# MainBoard.net
KiCad netlist of a schematic drawn in EAGLE
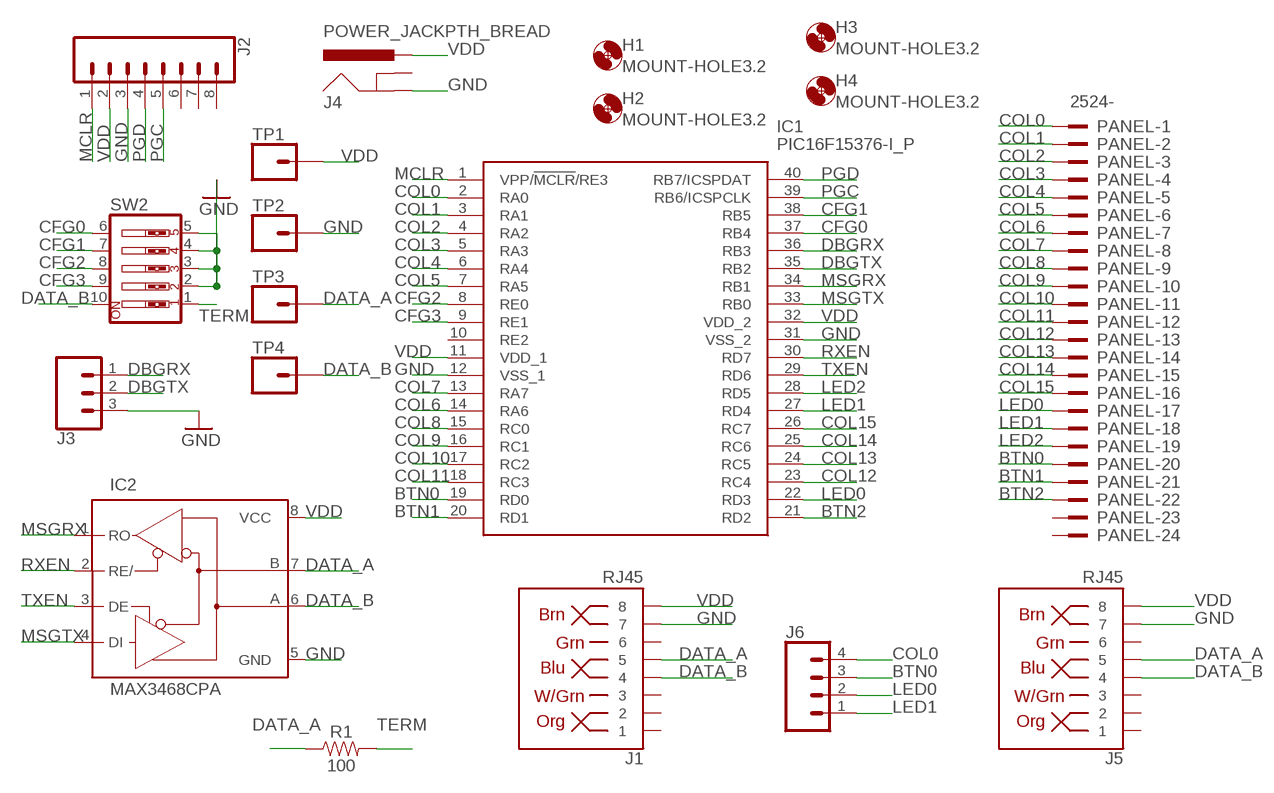
[diagram p0: schematic, sheet 1]

(export (version "E")
  (design (tool "Eeschema 10.0.6"))
  (components
    (comp (ref "H1")
      (value "MOUNT-HOLE3.2")
      (footprint "eagle-import:3,2")
      (libsource (lib "eagle-import") (part "MOUNT-HOLE3.2"))
    )
    (comp (ref "H2")
      (value "MOUNT-HOLE3.2")
      (footprint "eagle-import:3,2")
      (libsource (lib "eagle-import") (part "MOUNT-HOLE3.2"))
    )
    (comp (ref "H3")
      (value "MOUNT-HOLE3.2")
      (footprint "eagle-import:3,2")
      (libsource (lib "eagle-import") (part "MOUNT-HOLE3.2"))
    )
    (comp (ref "H4")
      (value "MOUNT-HOLE3.2")
      (footprint "eagle-import:3,2")
      (libsource (lib "eagle-import") (part "MOUNT-HOLE3.2"))
    )
    (comp (ref "IC1")
      (value "PIC16F15376-I_P")
      (footprint "eagle-import:DIP1550W56P254L5219H483Q40N")
      (fields (field (name "MANUFACTURER_PART_NUMBER") "PIC16F15376-I/P"))
      (libsource (lib "eagle-import") (part "PIC16F15376-I_P"))
    )
    (comp (ref "IC2")
      (value "MAX3468CPA")
      (footprint "eagle-import:DIL08")
      (libsource (lib "eagle-import") (part "MAX34PA68C"))
    )
    (comp (ref "J1")
      (value "RJ45")
      (footprint "eagle-import:RJ45-8")
      (libsource (lib "eagle-import") (part "RJ45-8"))
    )
    (comp (ref "J2")
      (value "CONN_08\"")
      (footprint "eagle-import:1X08")
      (libsource (lib "eagle-import") (part "CONN_08{dblquote}"))
    )
    (comp (ref "J3")
      (value "CONN_03")
      (footprint "eagle-import:1X03")
      (libsource (lib "eagle-import") (part "CONN_03"))
    )
    (comp (ref "J4")
      (value "POWER_JACKPTH_BREAD")
      (footprint "eagle-import:POWER_JACK_PTH_BREAD")
      (libsource (lib "eagle-import") (part "POWER_JACKPTH_BREAD"))
    )
    (comp (ref "J5")
      (value "RJ45")
      (footprint "eagle-import:RJ45-8")
      (libsource (lib "eagle-import") (part "RJ45-8"))
    )
    (comp (ref "J6")
      (value "CONN_04")
      (footprint "eagle-import:1X04")
      (libsource (lib "eagle-import") (part "CONN_04"))
    )
    (comp (ref "PANEL")
      (value "2524-")
      (footprint "eagle-import:PAK100_2500-24")
      (libsource (lib "eagle-import") (part "2524-"))
    )
    (comp (ref "R1")
      (value "100")
      (footprint "eagle-import:AXIAL-0.3")
      (libsource (lib "eagle-import") (part "100OHM-HORIZ-1/4W-1%"))
    )
    (comp (ref "SW2")
      (value "SW_DIP-5")
      (footprint "eagle-import:EDG-05")
      (libsource (lib "eagle-import") (part "SW_DIP-5"))
    )
    (comp (ref "TP1")
      (value "CONN_01")
      (footprint "eagle-import:1X01")
      (libsource (lib "eagle-import") (part "CONN_01"))
    )
    (comp (ref "TP2")
      (value "CONN_01")
      (footprint "eagle-import:1X01")
      (libsource (lib "eagle-import") (part "CONN_01"))
    )
    (comp (ref "TP3")
      (value "CONN_01")
      (footprint "eagle-import:1X01")
      (libsource (lib "eagle-import") (part "CONN_01"))
    )
    (comp (ref "TP4")
      (value "CONN_01")
      (footprint "eagle-import:1X01")
      (libsource (lib "eagle-import") (part "CONN_01"))
    )
  )
  (nets
    (net (code "1") (name "/BTN0") (class "Default")
      (node (ref "IC1") (pin "19") (pinfunction "RD0_19") (pintype "bidirectional"))
      (node (ref "J6") (pin "3") (pinfunction "3_3") (pintype "passive"))
      (node (ref "PANEL") (pin "20") (pinfunction "KL_20") (pintype "passive"))
    )
    (net (code "2") (name "/BTN1") (class "Default")
      (node (ref "IC1") (pin "20") (pinfunction "RD1_20") (pintype "bidirectional"))
      (node (ref "PANEL") (pin "21") (pinfunction "KL_21") (pintype "passive"))
    )
    (net (code "3") (name "/BTN2") (class "Default")
      (node (ref "IC1") (pin "21") (pinfunction "RD2_21") (pintype "bidirectional"))
      (node (ref "PANEL") (pin "22") (pinfunction "KL_22") (pintype "passive"))
    )
    (net (code "4") (name "/CFG0") (class "Default")
      (node (ref "IC1") (pin "37") (pinfunction "RB4_37") (pintype "bidirectional"))
      (node (ref "SW2") (pin "6") (pinfunction "6_6") (pintype "passive"))
    )
    (net (code "5") (name "/CFG1") (class "Default")
      (node (ref "IC1") (pin "38") (pinfunction "RB5_38") (pintype "bidirectional"))
      (node (ref "SW2") (pin "7") (pinfunction "7_7") (pintype "passive"))
    )
    (net (code "6") (name "/CFG2") (class "Default")
      (node (ref "IC1") (pin "8") (pinfunction "RE0_8") (pintype "bidirectional"))
      (node (ref "SW2") (pin "8") (pinfunction "8_8") (pintype "passive"))
    )
    (net (code "7") (name "/CFG3") (class "Default")
      (node (ref "IC1") (pin "9") (pinfunction "RE1_9") (pintype "bidirectional"))
      (node (ref "SW2") (pin "9") (pinfunction "9_9") (pintype "passive"))
    )
    (net (code "8") (name "/COL0") (class "Default")
      (node (ref "IC1") (pin "2") (pinfunction "RA0_2") (pintype "bidirectional"))
      (node (ref "J6") (pin "4") (pinfunction "4_4") (pintype "passive"))
      (node (ref "PANEL") (pin "1") (pinfunction "KL_1") (pintype "passive"))
    )
    (net (code "9") (name "/COL1") (class "Default")
      (node (ref "IC1") (pin "3") (pinfunction "RA1_3") (pintype "bidirectional"))
      (node (ref "PANEL") (pin "2") (pinfunction "KL_2") (pintype "passive"))
    )
    (net (code "10") (name "/COL2") (class "Default")
      (node (ref "IC1") (pin "4") (pinfunction "RA2_4") (pintype "bidirectional"))
      (node (ref "PANEL") (pin "3") (pinfunction "KL_3") (pintype "passive"))
    )
    (net (code "11") (name "/COL3") (class "Default")
      (node (ref "IC1") (pin "5") (pinfunction "RA3_5") (pintype "bidirectional"))
      (node (ref "PANEL") (pin "4") (pinfunction "KL_4") (pintype "passive"))
    )
    (net (code "12") (name "/COL4") (class "Default")
      (node (ref "IC1") (pin "6") (pinfunction "RA4_6") (pintype "bidirectional"))
      (node (ref "PANEL") (pin "5") (pinfunction "KL_5") (pintype "passive"))
    )
    (net (code "13") (name "/COL5") (class "Default")
      (node (ref "IC1") (pin "7") (pinfunction "RA5_7") (pintype "bidirectional"))
      (node (ref "PANEL") (pin "6") (pinfunction "KL_6") (pintype "passive"))
    )
    (net (code "14") (name "/COL6") (class "Default")
      (node (ref "IC1") (pin "14") (pinfunction "RA6_14") (pintype "bidirectional"))
      (node (ref "PANEL") (pin "7") (pinfunction "KL_7") (pintype "passive"))
    )
    (net (code "15") (name "/COL7") (class "Default")
      (node (ref "IC1") (pin "13") (pinfunction "RA7_13") (pintype "bidirectional"))
      (node (ref "PANEL") (pin "8") (pinfunction "KL_8") (pintype "passive"))
    )
    (net (code "16") (name "/COL8") (class "Default")
      (node (ref "IC1") (pin "15") (pinfunction "RC0_15") (pintype "bidirectional"))
      (node (ref "PANEL") (pin "9") (pinfunction "KL_9") (pintype "passive"))
    )
    (net (code "17") (name "/COL9") (class "Default")
      (node (ref "IC1") (pin "16") (pinfunction "RC1_16") (pintype "bidirectional"))
      (node (ref "PANEL") (pin "10") (pinfunction "KL_10") (pintype "passive"))
    )
    (net (code "18") (name "/COL10") (class "Default")
      (node (ref "IC1") (pin "17") (pinfunction "RC2_17") (pintype "bidirectional"))
      (node (ref "PANEL") (pin "11") (pinfunction "KL_11") (pintype "passive"))
    )
    (net (code "19") (name "/COL11") (class "Default")
      (node (ref "IC1") (pin "18") (pinfunction "RC3_18") (pintype "bidirectional"))
      (node (ref "PANEL") (pin "12") (pinfunction "KL_12") (pintype "passive"))
    )
    (net (code "20") (name "/COL12") (class "Default")
      (node (ref "IC1") (pin "23") (pinfunction "RC4_23") (pintype "bidirectional"))
      (node (ref "PANEL") (pin "13") (pinfunction "KL_13") (pintype "passive"))
    )
    (net (code "21") (name "/COL13") (class "Default")
      (node (ref "IC1") (pin "24") (pinfunction "RC5_24") (pintype "bidirectional"))
      (node (ref "PANEL") (pin "14") (pinfunction "KL_14") (pintype "passive"))
    )
    (net (code "22") (name "/COL14") (class "Default")
      (node (ref "IC1") (pin "25") (pinfunction "RC6_25") (pintype "bidirectional"))
      (node (ref "PANEL") (pin "15") (pinfunction "KL_15") (pintype "passive"))
    )
    (net (code "23") (name "/COL15") (class "Default")
      (node (ref "IC1") (pin "26") (pinfunction "RC7_26") (pintype "bidirectional"))
      (node (ref "PANEL") (pin "16") (pinfunction "KL_16") (pintype "passive"))
    )
    (net (code "24") (name "/DATA_A") (class "Default")
      (node (ref "IC2") (pin "7") (pinfunction "B_7") (pintype "passive"))
      (node (ref "J1") (pin "5") (pinfunction "5_5") (pintype "bidirectional"))
      (node (ref "J5") (pin "5") (pinfunction "5_5") (pintype "bidirectional"))
      (node (ref "R1") (pin "P$1") (pinfunction "1_P$1") (pintype "passive"))
      (node (ref "TP3") (pin "1") (pinfunction "1_1") (pintype "passive"))
    )
    (net (code "25") (name "/DATA_B") (class "Default")
      (node (ref "IC2") (pin "6") (pinfunction "A_6") (pintype "passive"))
      (node (ref "J1") (pin "4") (pinfunction "4_4") (pintype "bidirectional"))
      (node (ref "J5") (pin "4") (pinfunction "4_4") (pintype "bidirectional"))
      (node (ref "SW2") (pin "10") (pinfunction "10_10") (pintype "passive"))
      (node (ref "TP4") (pin "1") (pinfunction "1_1") (pintype "passive"))
    )
    (net (code "26") (name "/DBGRX") (class "Default")
      (node (ref "IC1") (pin "36") (pinfunction "RB3_36") (pintype "bidirectional"))
      (node (ref "J3") (pin "1") (pinfunction "1_1") (pintype "passive"))
    )
    (net (code "27") (name "/DBGTX") (class "Default")
      (node (ref "IC1") (pin "35") (pinfunction "RB2_35") (pintype "bidirectional"))
      (node (ref "J3") (pin "2") (pinfunction "2_2") (pintype "passive"))
    )
    (net (code "28") (name "/LED0") (class "Default")
      (node (ref "IC1") (pin "22") (pinfunction "RD3_22") (pintype "bidirectional"))
      (node (ref "J6") (pin "2") (pinfunction "2_2") (pintype "passive"))
      (node (ref "PANEL") (pin "17") (pinfunction "KL_17") (pintype "passive"))
    )
    (net (code "29") (name "/LED1") (class "Default")
      (node (ref "IC1") (pin "27") (pinfunction "RD4_27") (pintype "bidirectional"))
      (node (ref "J6") (pin "1") (pinfunction "1_1") (pintype "passive"))
      (node (ref "PANEL") (pin "18") (pinfunction "KL_18") (pintype "passive"))
    )
    (net (code "30") (name "/LED2") (class "Default")
      (node (ref "IC1") (pin "28") (pinfunction "RD5_28") (pintype "bidirectional"))
      (node (ref "PANEL") (pin "19") (pinfunction "KL_19") (pintype "passive"))
    )
    (net (code "31") (name "/MCLR") (class "Default")
      (node (ref "IC1") (pin "1") (pinfunction "VPP/~{MCLR}/RE3_1") (pintype "bidirectional"))
      (node (ref "J2") (pin "1") (pinfunction "1_1") (pintype "passive"))
    )
    (net (code "32") (name "/MSGRX") (class "Default")
      (node (ref "IC1") (pin "34") (pinfunction "RB1_34") (pintype "bidirectional"))
      (node (ref "IC2") (pin "1") (pinfunction "RO_1") (pintype "output"))
    )
    (net (code "33") (name "/MSGTX") (class "Default")
      (node (ref "IC1") (pin "33") (pinfunction "RB0_33") (pintype "bidirectional"))
      (node (ref "IC2") (pin "4") (pinfunction "DI_4") (pintype "input"))
    )
    (net (code "34") (name "/PGC") (class "Default")
      (node (ref "IC1") (pin "39") (pinfunction "RB6/ICSPCLK_39") (pintype "bidirectional"))
      (node (ref "J2") (pin "5") (pinfunction "5_5") (pintype "passive"))
    )
    (net (code "35") (name "/PGD") (class "Default")
      (node (ref "IC1") (pin "40") (pinfunction "RB7/ICSPDAT_40") (pintype "bidirectional"))
      (node (ref "J2") (pin "4") (pinfunction "4_4") (pintype "passive"))
    )
    (net (code "36") (name "/RXEN") (class "Default")
      (node (ref "IC1") (pin "30") (pinfunction "RD7_30") (pintype "bidirectional"))
      (node (ref "IC2") (pin "2") (pinfunction "RE/_2") (pintype "input"))
    )
    (net (code "37") (name "/TERM") (class "Default")
      (node (ref "R1") (pin "P$2") (pinfunction "2_P$2") (pintype "passive"))
      (node (ref "SW2") (pin "1") (pinfunction "1_1") (pintype "passive"))
    )
    (net (code "38") (name "/TXEN") (class "Default")
      (node (ref "IC1") (pin "29") (pinfunction "RD6_29") (pintype "bidirectional"))
      (node (ref "IC2") (pin "3") (pinfunction "DE_3") (pintype "input"))
    )
    (net (code "39") (name "/VDD") (class "Default")
      (node (ref "IC1") (pin "11") (pinfunction "VDD_1_11") (pintype "power_in"))
      (node (ref "IC1") (pin "32") (pinfunction "VDD_2_32") (pintype "power_in"))
      (node (ref "IC2") (pin "8") (pinfunction "VCC_8") (pintype "power_in"))
      (node (ref "J1") (pin "8") (pinfunction "8_8") (pintype "bidirectional"))
      (node (ref "J2") (pin "2") (pinfunction "2_2") (pintype "passive"))
      (node (ref "J4") (pin "PWR") (pinfunction "PWR_PWR") (pintype "bidirectional"))
      (node (ref "J5") (pin "8") (pinfunction "8_8") (pintype "bidirectional"))
      (node (ref "TP1") (pin "1") (pinfunction "1_1") (pintype "passive"))
    )
    (net (code "40") (name "GND") (class "Default")
      (node (ref "IC1") (pin "12") (pinfunction "VSS_1_12") (pintype "power_in"))
      (node (ref "IC1") (pin "31") (pinfunction "VSS_2_31") (pintype "power_in"))
      (node (ref "IC2") (pin "5") (pinfunction "GND_5") (pintype "power_in"))
      (node (ref "J1") (pin "7") (pinfunction "7_7") (pintype "bidirectional"))
      (node (ref "J2") (pin "3") (pinfunction "3_3") (pintype "passive"))
      (node (ref "J3") (pin "3") (pinfunction "3_3") (pintype "passive"))
      (node (ref "J4") (pin "GND") (pinfunction "GND_GND") (pintype "bidirectional"))
      (node (ref "J5") (pin "7") (pinfunction "7_7") (pintype "bidirectional"))
      (node (ref "SW2") (pin "2") (pinfunction "2_2") (pintype "passive"))
      (node (ref "SW2") (pin "3") (pinfunction "3_3") (pintype "passive"))
      (node (ref "SW2") (pin "4") (pinfunction "4_4") (pintype "passive"))
      (node (ref "SW2") (pin "5") (pinfunction "5_5") (pintype "passive"))
      (node (ref "TP2") (pin "1") (pinfunction "1_1") (pintype "passive"))
    )
    (net (code "41") (name "unconnected-(IC1-RE2-Pad10)") (class "Default")
      (node (ref "IC1") (pin "10") (pinfunction "RE2_10") (pintype "bidirectional"))
    )
    (net (code "42") (name "unconnected-(J1-Pad1)") (class "Default")
      (node (ref "J1") (pin "1") (pinfunction "1_1") (pintype "bidirectional"))
    )
    (net (code "43") (name "unconnected-(J1-Pad2)") (class "Default")
      (node (ref "J1") (pin "2") (pinfunction "2_2") (pintype "bidirectional"))
    )
    (net (code "44") (name "unconnected-(J1-Pad3)") (class "Default")
      (node (ref "J1") (pin "3") (pinfunction "3_3") (pintype "bidirectional"))
    )
    (net (code "45") (name "unconnected-(J1-Pad6)") (class "Default")
      (node (ref "J1") (pin "6") (pinfunction "6_6") (pintype "bidirectional"))
    )
    (net (code "46") (name "unconnected-(J2-Pad6)") (class "Default")
      (node (ref "J2") (pin "6") (pinfunction "6_6") (pintype "passive"))
    )
    (net (code "47") (name "unconnected-(J2-Pad7)") (class "Default")
      (node (ref "J2") (pin "7") (pinfunction "7_7") (pintype "passive"))
    )
    (net (code "48") (name "unconnected-(J2-Pad8)") (class "Default")
      (node (ref "J2") (pin "8") (pinfunction "8_8") (pintype "passive"))
    )
    (net (code "49") (name "unconnected-(J4-PadGNDBREAK)") (class "Default")
      (node (ref "J4") (pin "GNDBREAK") (pinfunction "GNDBREAK_GNDBREAK") (pintype "bidirectional"))
    )
    (net (code "50") (name "unconnected-(J5-Pad1)") (class "Default")
      (node (ref "J5") (pin "1") (pinfunction "1_1") (pintype "bidirectional"))
    )
    (net (code "51") (name "unconnected-(J5-Pad2)") (class "Default")
      (node (ref "J5") (pin "2") (pinfunction "2_2") (pintype "bidirectional"))
    )
    (net (code "52") (name "unconnected-(J5-Pad3)") (class "Default")
      (node (ref "J5") (pin "3") (pinfunction "3_3") (pintype "bidirectional"))
    )
    (net (code "53") (name "unconnected-(J5-Pad6)") (class "Default")
      (node (ref "J5") (pin "6") (pinfunction "6_6") (pintype "bidirectional"))
    )
    (net (code "54") (name "unconnected-(PANELP-KL-Pad23)") (class "Default")
      (node (ref "PANEL") (pin "23") (pinfunction "KL_23") (pintype "passive"))
    )
    (net (code "55") (name "unconnected-(PANELQ-KL-Pad24)") (class "Default")
      (node (ref "PANEL") (pin "24") (pinfunction "KL_24") (pintype "passive"))
    )
  )
)
